# Pure_VCO.net
KiCad netlist of a schematic drawn in EAGLE
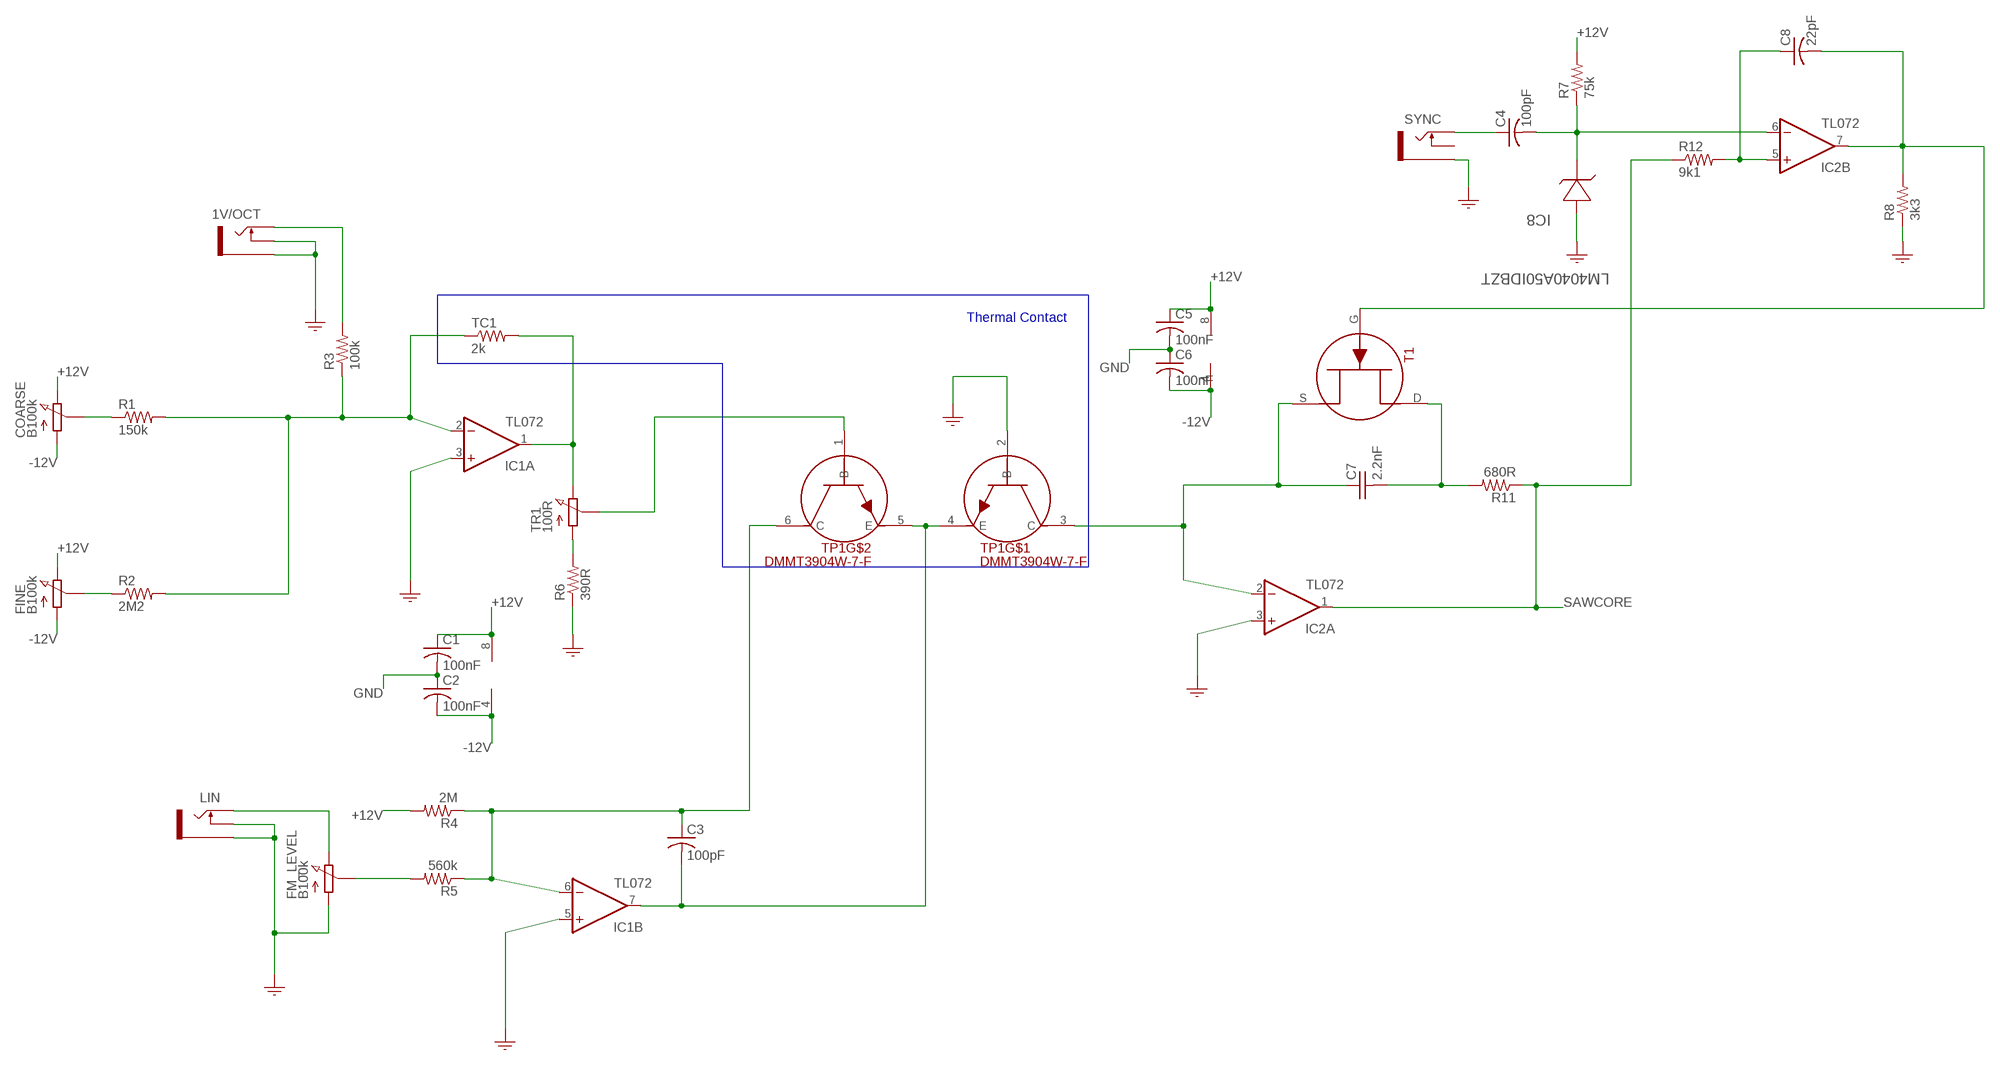
[diagram p0: schematic, sheet 1]
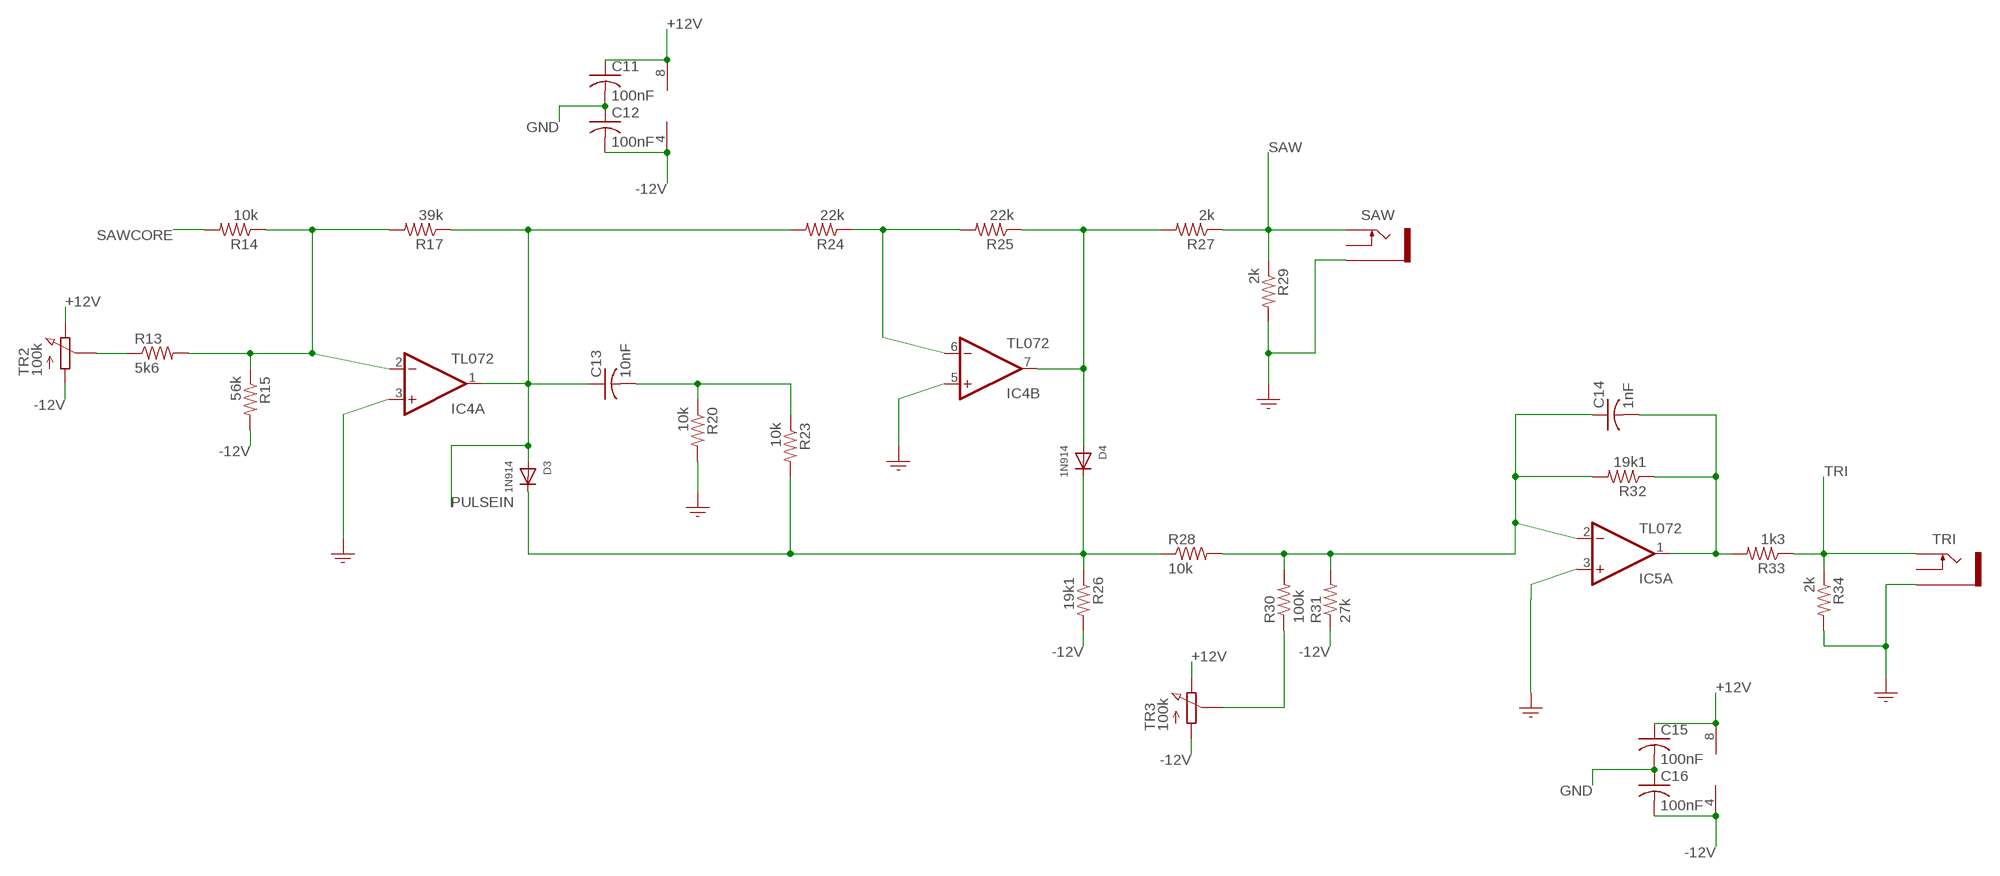
[diagram p1: schematic, sheet 2]
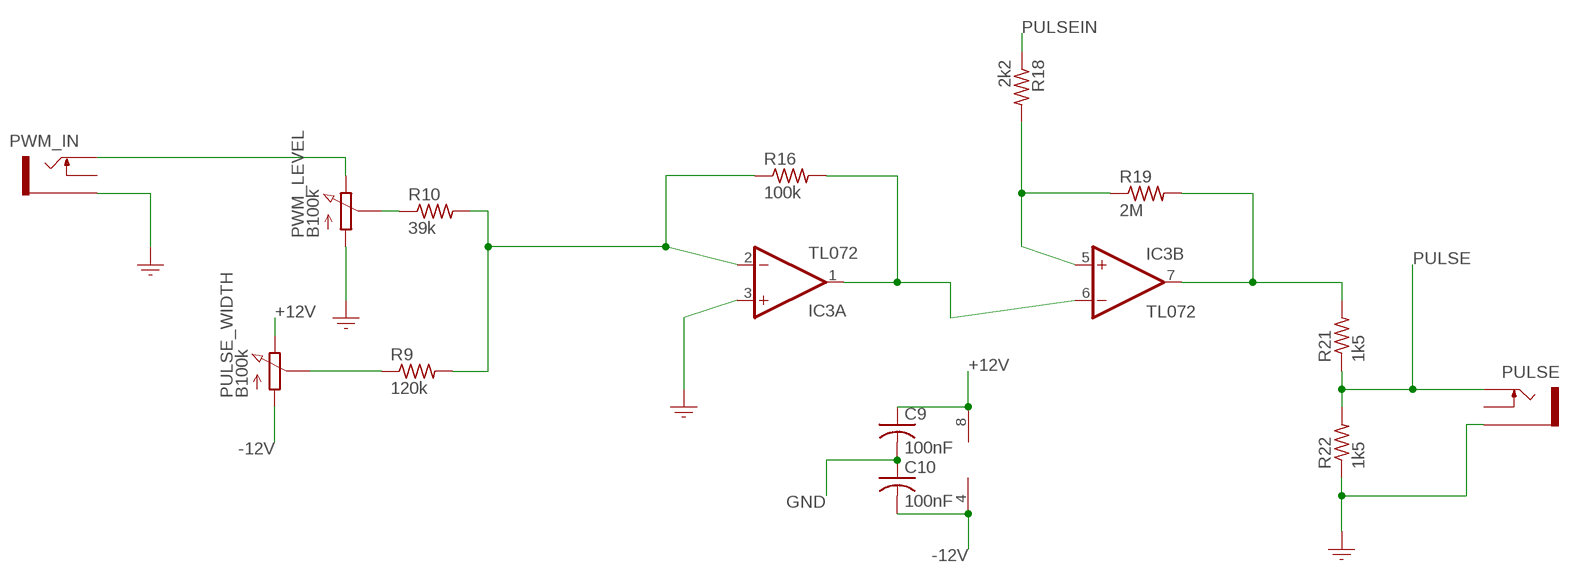
[diagram p2: schematic, sheet 3]
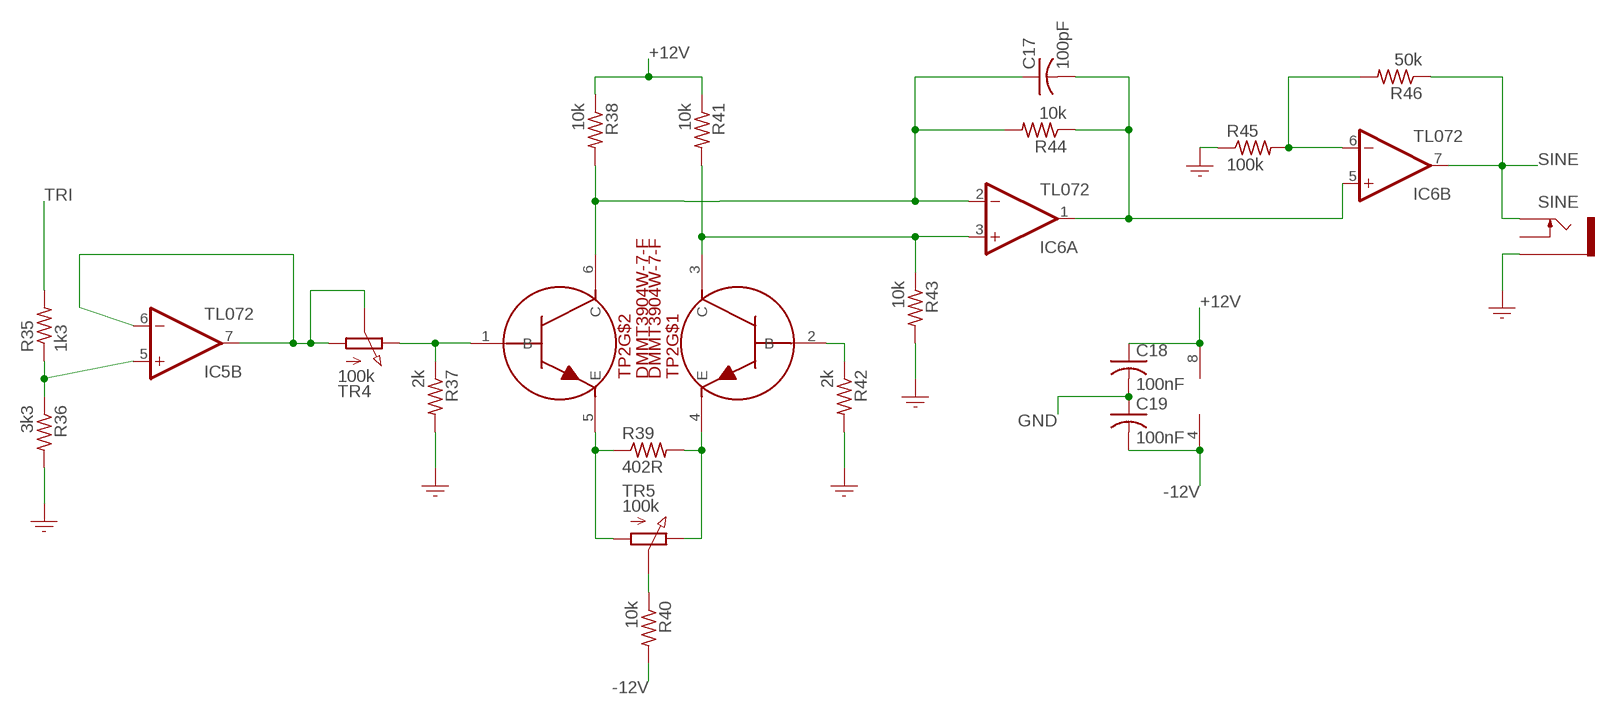
[diagram p3: schematic, sheet 4]
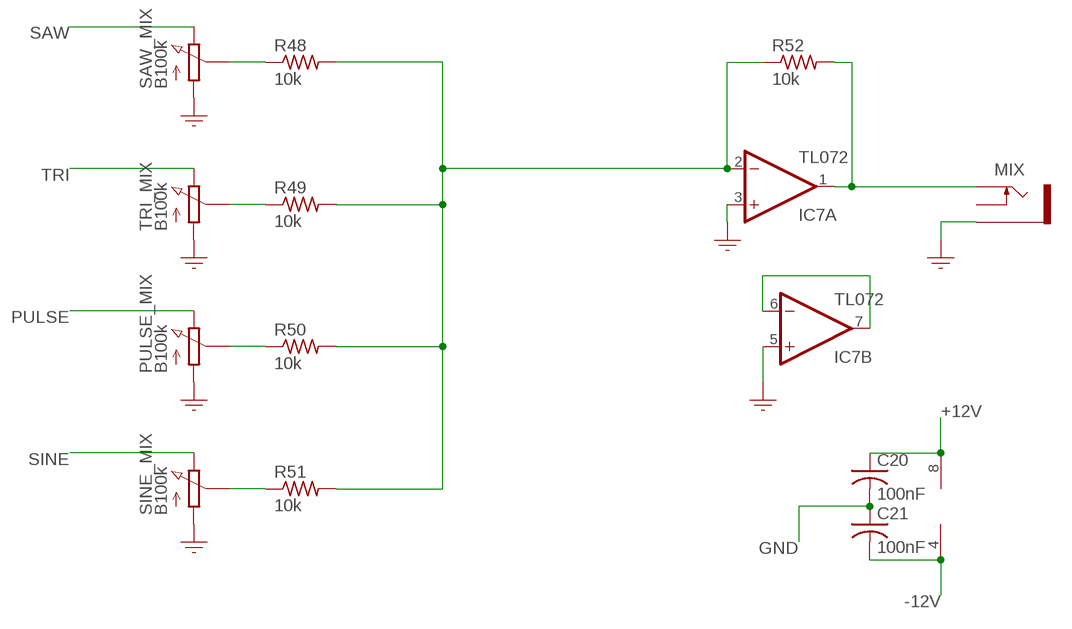
[diagram p4: schematic, sheet 5]
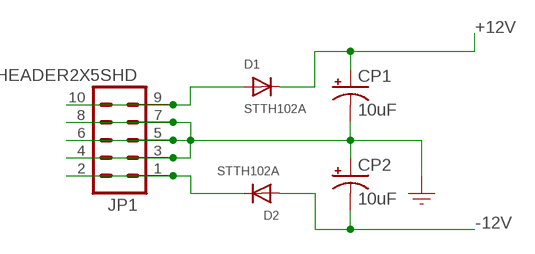
[diagram p5: schematic, sheet 6]

(export (version "E")
  (design (tool "Eeschema 10.0.6"))
  (components
    (comp (ref "1V/OCT")
      (value "PJ301M-12")
      (footprint "eagle-import:PJ301M-12")
      (libsource (lib "eagle-import") (part "SOCKET_MONO_3.5MMPJ301M-12"))
    )
    (comp (ref "C1")
      (value "100nF")
      (footprint "eagle-import:C0805")
      (libsource (lib "eagle-import") (part "CAPACITOR-USC0805"))
    )
    (comp (ref "C2")
      (value "100nF")
      (footprint "eagle-import:C0805")
      (libsource (lib "eagle-import") (part "CAPACITOR-USC0805"))
    )
    (comp (ref "C3")
      (value "100pF")
      (footprint "eagle-import:C0805")
      (libsource (lib "eagle-import") (part "CAPACITOR-USC0805"))
    )
    (comp (ref "C4")
      (value "100pF")
      (footprint "eagle-import:C0805")
      (libsource (lib "eagle-import") (part "CAPACITOR-USC0805"))
    )
    (comp (ref "C5")
      (value "100nF")
      (footprint "eagle-import:C0805")
      (libsource (lib "eagle-import") (part "CAPACITOR-USC0805"))
    )
    (comp (ref "C6")
      (value "100nF")
      (footprint "eagle-import:C0805")
      (libsource (lib "eagle-import") (part "CAPACITOR-USC0805"))
    )
    (comp (ref "C7")
      (value "2.2nF")
      (footprint "eagle-import:POLY_CAP")
      (libsource (lib "eagle-import") (part "CAPACITOR_POLYFILM"))
    )
    (comp (ref "C8")
      (value "22pF")
      (footprint "eagle-import:C0805")
      (libsource (lib "eagle-import") (part "CAPACITOR-USC0805"))
    )
    (comp (ref "COARSE")
      (value "B100k")
      (footprint "eagle-import:POT_9MM_RED_KNOB")
      (libsource (lib "eagle-import") (part "RESISTOR_VARIABLEPOT_9MM_RED_KNOB"))
    )
    (comp (ref "FINE")
      (value "B100k")
      (footprint "eagle-import:POT_9MM_RED_MXR_KNOB")
      (libsource (lib "eagle-import") (part "RESISTOR_VARIABLEPOT_9MM_RED_MXR_KNOB"))
    )
    (comp (ref "FM_LEVEL")
      (value "B100k")
      (footprint "eagle-import:POT_9MM_GREEN_KNOB")
      (libsource (lib "eagle-import") (part "RESISTOR_VARIABLEPOT_9MM_GREEN_KNOB"))
    )
    (comp (ref "IC1")
      (value "TL072")
      (footprint "eagle-import:SO08")
      (libsource (lib "eagle-import") (part "OPAMP_DUALD"))
    )
    (comp (ref "IC2")
      (value "TL072")
      (footprint "eagle-import:SO08")
      (libsource (lib "eagle-import") (part "OPAMP_DUALD"))
    )
    (comp (ref "IC8")
      (value "LM4040A50IDBZT")
      (footprint "eagle-import:SOT95P237X112-3N")
      (libsource (lib "eagle-import") (part "VOLTAGE_REF"))
    )
    (comp (ref "LIN")
      (value "PJ301M-12")
      (footprint "eagle-import:PJ301M-12")
      (libsource (lib "eagle-import") (part "SOCKET_MONO_3.5MMPJ301M-12"))
    )
    (comp (ref "R1")
      (value "150k")
      (footprint "eagle-import:R0805")
      (libsource (lib "eagle-import") (part "RESISTOR_USR0805"))
    )
    (comp (ref "R2")
      (value "2M2")
      (footprint "eagle-import:R0805")
      (libsource (lib "eagle-import") (part "RESISTOR_USR0805"))
    )
    (comp (ref "R3")
      (value "100k")
      (footprint "eagle-import:R0805")
      (libsource (lib "eagle-import") (part "RESISTOR_USR0805"))
    )
    (comp (ref "R4")
      (value "2M")
      (footprint "eagle-import:R0805")
      (libsource (lib "eagle-import") (part "RESISTOR_USR0805"))
    )
    (comp (ref "R5")
      (value "560k")
      (footprint "eagle-import:R0805")
      (libsource (lib "eagle-import") (part "RESISTOR_USR0805"))
    )
    (comp (ref "R6")
      (value "390R")
      (footprint "eagle-import:R0805")
      (libsource (lib "eagle-import") (part "RESISTOR_USR0805"))
    )
    (comp (ref "R7")
      (value "75k")
      (footprint "eagle-import:R0805")
      (libsource (lib "eagle-import") (part "RESISTOR_USR0805"))
    )
    (comp (ref "R8")
      (value "3k3")
      (footprint "eagle-import:R0805")
      (libsource (lib "eagle-import") (part "RESISTOR_USR0805"))
    )
    (comp (ref "R11")
      (value "680R")
      (footprint "eagle-import:R0805")
      (libsource (lib "eagle-import") (part "RESISTOR_USR0805"))
    )
    (comp (ref "R12")
      (value "9k1")
      (footprint "eagle-import:R0805")
      (libsource (lib "eagle-import") (part "RESISTOR_USR0805"))
    )
    (comp (ref "SYNC")
      (value "PJ301M-12")
      (footprint "eagle-import:PJ301M-12")
      (libsource (lib "eagle-import") (part "SOCKET_MONO_3.5MMPJ301M-12"))
    )
    (comp (ref "T1")
      (value "MMBFJ309")
      (footprint "eagle-import:N_CHN")
      (libsource (lib "eagle-import") (part "TRANSISTOR_JFET_N_CHN"))
    )
    (comp (ref "TC1")
      (value "2k")
      (footprint "eagle-import:0207_8.5")
      (libsource (lib "eagle-import") (part "RESISTOR_US0207/8.5"))
    )
    (comp (ref "TP1")
      (value "DMMT3904W-7-F")
      (footprint "eagle-import:TRANS_PAIR")
      (libsource (lib "eagle-import") (part "TRANSISTOR_PAIR_NPN"))
    )
    (comp (ref "TR1")
      (value "100R")
      (footprint "eagle-import:TRIMMER_TH")
      (libsource (lib "eagle-import") (part "RESISTOR_VARIABLETRIMMER_TH"))
    )
    (comp (ref "C11")
      (value "100nF")
      (footprint "eagle-import:C0805")
      (libsource (lib "eagle-import") (part "CAPACITOR-USC0805"))
    )
    (comp (ref "C12")
      (value "100nF")
      (footprint "eagle-import:C0805")
      (libsource (lib "eagle-import") (part "CAPACITOR-USC0805"))
    )
    (comp (ref "C13")
      (value "10nF")
      (footprint "eagle-import:C0805")
      (libsource (lib "eagle-import") (part "CAPACITOR-USC0805"))
    )
    (comp (ref "C14")
      (value "1nF")
      (footprint "eagle-import:C0805")
      (libsource (lib "eagle-import") (part "CAPACITOR-USC0805"))
    )
    (comp (ref "C15")
      (value "100nF")
      (footprint "eagle-import:C0805")
      (libsource (lib "eagle-import") (part "CAPACITOR-USC0805"))
    )
    (comp (ref "C16")
      (value "100nF")
      (footprint "eagle-import:C0805")
      (libsource (lib "eagle-import") (part "CAPACITOR-USC0805"))
    )
    (comp (ref "D3")
      (value "1N914")
      (footprint "eagle-import:SOD-323F")
      (libsource (lib "eagle-import") (part "DIODESOD-323F"))
    )
    (comp (ref "D4")
      (value "1N914")
      (footprint "eagle-import:SOD-323F")
      (libsource (lib "eagle-import") (part "DIODESOD-323F"))
    )
    (comp (ref "IC4")
      (value "TL072")
      (footprint "eagle-import:SO08")
      (libsource (lib "eagle-import") (part "OPAMP_DUALD"))
    )
    (comp (ref "IC5")
      (value "TL072")
      (footprint "eagle-import:SO08")
      (libsource (lib "eagle-import") (part "OPAMP_DUALD"))
    )
    (comp (ref "R13")
      (value "5k6")
      (footprint "eagle-import:R0805")
      (libsource (lib "eagle-import") (part "RESISTOR_USR0805"))
    )
    (comp (ref "R14")
      (value "10k")
      (footprint "eagle-import:R0805")
      (libsource (lib "eagle-import") (part "RESISTOR_USR0805"))
    )
    (comp (ref "R15")
      (value "56k")
      (footprint "eagle-import:R0805")
      (libsource (lib "eagle-import") (part "RESISTOR_USR0805"))
    )
    (comp (ref "R17")
      (value "39k")
      (footprint "eagle-import:R0805")
      (libsource (lib "eagle-import") (part "RESISTOR_USR0805"))
    )
    (comp (ref "R20")
      (value "10k")
      (footprint "eagle-import:R0805")
      (libsource (lib "eagle-import") (part "RESISTOR_USR0805"))
    )
    (comp (ref "R23")
      (value "10k")
      (footprint "eagle-import:R0805")
      (libsource (lib "eagle-import") (part "RESISTOR_USR0805"))
    )
    (comp (ref "R24")
      (value "22k")
      (footprint "eagle-import:R0805")
      (libsource (lib "eagle-import") (part "RESISTOR_USR0805"))
    )
    (comp (ref "R25")
      (value "22k")
      (footprint "eagle-import:R0805")
      (libsource (lib "eagle-import") (part "RESISTOR_USR0805"))
    )
    (comp (ref "R26")
      (value "19k1")
      (footprint "eagle-import:R0805")
      (libsource (lib "eagle-import") (part "RESISTOR_USR0805"))
    )
    (comp (ref "R27")
      (value "2k")
      (footprint "eagle-import:R0805")
      (libsource (lib "eagle-import") (part "RESISTOR_USR0805"))
    )
    (comp (ref "R28")
      (value "10k")
      (footprint "eagle-import:R0805")
      (libsource (lib "eagle-import") (part "RESISTOR_USR0805"))
    )
    (comp (ref "R29")
      (value "2k")
      (footprint "eagle-import:R0805")
      (libsource (lib "eagle-import") (part "RESISTOR_USR0805"))
    )
    (comp (ref "R30")
      (value "100k")
      (footprint "eagle-import:R0805")
      (libsource (lib "eagle-import") (part "RESISTOR_USR0805"))
    )
    (comp (ref "R31")
      (value "27k")
      (footprint "eagle-import:R0805")
      (libsource (lib "eagle-import") (part "RESISTOR_USR0805"))
    )
    (comp (ref "R32")
      (value "19k1")
      (footprint "eagle-import:R0805")
      (libsource (lib "eagle-import") (part "RESISTOR_USR0805"))
    )
    (comp (ref "R33")
      (value "1k3")
      (footprint "eagle-import:R0805")
      (libsource (lib "eagle-import") (part "RESISTOR_USR0805"))
    )
    (comp (ref "R34")
      (value "2k")
      (footprint "eagle-import:R0805")
      (libsource (lib "eagle-import") (part "RESISTOR_USR0805"))
    )
    (comp (ref "SAW")
      (value "PJ301M-12")
      (footprint "eagle-import:PJ301M-12")
      (libsource (lib "eagle-import") (part "SOCKET_MONO_3.5MMPJ301M-12"))
    )
    (comp (ref "TR2")
      (value "100k")
      (footprint "eagle-import:TRIMMER_TH")
      (libsource (lib "eagle-import") (part "RESISTOR_VARIABLETRIMMER_TH"))
    )
    (comp (ref "TR3")
      (value "100k")
      (footprint "eagle-import:TRIMMER_TH")
      (libsource (lib "eagle-import") (part "RESISTOR_VARIABLETRIMMER_TH"))
    )
    (comp (ref "TRI")
      (value "PJ301M-12")
      (footprint "eagle-import:PJ301M-12")
      (libsource (lib "eagle-import") (part "SOCKET_MONO_3.5MMPJ301M-12"))
    )
    (comp (ref "C17")
      (value "100pF")
      (footprint "eagle-import:C0805")
      (libsource (lib "eagle-import") (part "CAPACITOR-USC0805"))
    )
    (comp (ref "C18")
      (value "100nF")
      (footprint "eagle-import:C0805")
      (libsource (lib "eagle-import") (part "CAPACITOR-USC0805"))
    )
    (comp (ref "C19")
      (value "100nF")
      (footprint "eagle-import:C0805")
      (libsource (lib "eagle-import") (part "CAPACITOR-USC0805"))
    )
    (comp (ref "IC6")
      (value "TL072")
      (footprint "eagle-import:SO08")
      (libsource (lib "eagle-import") (part "OPAMP_DUALD"))
    )
    (comp (ref "R35")
      (value "1k3")
      (footprint "eagle-import:R0805")
      (libsource (lib "eagle-import") (part "RESISTOR_USR0805"))
    )
    (comp (ref "R36")
      (value "3k3")
      (footprint "eagle-import:R0805")
      (libsource (lib "eagle-import") (part "RESISTOR_USR0805"))
    )
    (comp (ref "R37")
      (value "2k")
      (footprint "eagle-import:R0805")
      (libsource (lib "eagle-import") (part "RESISTOR_USR0805"))
    )
    (comp (ref "R38")
      (value "10k")
      (footprint "eagle-import:R0805")
      (libsource (lib "eagle-import") (part "RESISTOR_USR0805"))
    )
    (comp (ref "R39")
      (value "402R")
      (footprint "eagle-import:R0805")
      (libsource (lib "eagle-import") (part "RESISTOR_USR0805"))
    )
    (comp (ref "R40")
      (value "10k")
      (footprint "eagle-import:R0805")
      (libsource (lib "eagle-import") (part "RESISTOR_USR0805"))
    )
    (comp (ref "R41")
      (value "10k")
      (footprint "eagle-import:R0805")
      (libsource (lib "eagle-import") (part "RESISTOR_USR0805"))
    )
    (comp (ref "R42")
      (value "2k")
      (footprint "eagle-import:R0805")
      (libsource (lib "eagle-import") (part "RESISTOR_USR0805"))
    )
    (comp (ref "R43")
      (value "10k")
      (footprint "eagle-import:R0805")
      (libsource (lib "eagle-import") (part "RESISTOR_USR0805"))
    )
    (comp (ref "R44")
      (value "10k")
      (footprint "eagle-import:R0805")
      (libsource (lib "eagle-import") (part "RESISTOR_USR0805"))
    )
    (comp (ref "R45")
      (value "100k")
      (footprint "eagle-import:R0805")
      (libsource (lib "eagle-import") (part "RESISTOR_USR0805"))
    )
    (comp (ref "R46")
      (value "50k")
      (footprint "eagle-import:R0805")
      (libsource (lib "eagle-import") (part "RESISTOR_USR0805"))
    )
    (comp (ref "SINE")
      (value "PJ301M-12")
      (footprint "eagle-import:PJ301M-12")
      (libsource (lib "eagle-import") (part "SOCKET_MONO_3.5MMPJ301M-12"))
    )
    (comp (ref "TP2")
      (value "DMMT3904W-7-F")
      (footprint "eagle-import:TRANS_PAIR")
      (libsource (lib "eagle-import") (part "TRANSISTOR_PAIR_NPN"))
    )
    (comp (ref "TR4")
      (value "100k")
      (footprint "eagle-import:TRIMMER_TH")
      (libsource (lib "eagle-import") (part "RESISTOR_VARIABLETRIMMER_TH"))
    )
    (comp (ref "TR5")
      (value "100k")
      (footprint "eagle-import:TRIMMER_TH")
      (libsource (lib "eagle-import") (part "RESISTOR_VARIABLETRIMMER_TH"))
    )
    (comp (ref "C20")
      (value "100nF")
      (footprint "eagle-import:C0805")
      (libsource (lib "eagle-import") (part "CAPACITOR-USC0805"))
    )
    (comp (ref "C21")
      (value "100nF")
      (footprint "eagle-import:C0805")
      (libsource (lib "eagle-import") (part "CAPACITOR-USC0805"))
    )
    (comp (ref "IC7")
      (value "TL072")
      (footprint "eagle-import:SO08")
      (libsource (lib "eagle-import") (part "OPAMP_DUALD"))
    )
    (comp (ref "MIX")
      (value "PJ301M-12")
      (footprint "eagle-import:PJ301M-12")
      (libsource (lib "eagle-import") (part "SOCKET_MONO_3.5MMPJ301M-12"))
    )
    (comp (ref "PULSE_MIX")
      (value "B100k")
      (footprint "eagle-import:POT_9MM_BLUE_KNOB")
      (libsource (lib "eagle-import") (part "RESISTOR_VARIABLEPOT_9MM_BLUE_KNOB"))
    )
    (comp (ref "R48")
      (value "10k")
      (footprint "eagle-import:R0805")
      (libsource (lib "eagle-import") (part "RESISTOR_USR0805"))
    )
    (comp (ref "R49")
      (value "10k")
      (footprint "eagle-import:R0805")
      (libsource (lib "eagle-import") (part "RESISTOR_USR0805"))
    )
    (comp (ref "R50")
      (value "10k")
      (footprint "eagle-import:R0805")
      (libsource (lib "eagle-import") (part "RESISTOR_USR0805"))
    )
    (comp (ref "R51")
      (value "10k")
      (footprint "eagle-import:R0805")
      (libsource (lib "eagle-import") (part "RESISTOR_USR0805"))
    )
    (comp (ref "R52")
      (value "10k")
      (footprint "eagle-import:R0805")
      (libsource (lib "eagle-import") (part "RESISTOR_USR0805"))
    )
    (comp (ref "SAW_MIX")
      (value "B100k")
      (footprint "eagle-import:POT_9MM_BLUE_KNOB")
      (libsource (lib "eagle-import") (part "RESISTOR_VARIABLEPOT_9MM_BLUE_KNOB"))
    )
    (comp (ref "SINE_MIX")
      (value "B100k")
      (footprint "eagle-import:POT_9MM_BLUE_KNOB")
      (libsource (lib "eagle-import") (part "RESISTOR_VARIABLEPOT_9MM_BLUE_KNOB"))
    )
    (comp (ref "TRI_MIX")
      (value "B100k")
      (footprint "eagle-import:POT_9MM_BLUE_KNOB")
      (libsource (lib "eagle-import") (part "RESISTOR_VARIABLEPOT_9MM_BLUE_KNOB"))
    )
    (comp (ref "C9")
      (value "100nF")
      (footprint "eagle-import:C0805")
      (libsource (lib "eagle-import") (part "CAPACITOR-USC0805"))
    )
    (comp (ref "C10")
      (value "100nF")
      (footprint "eagle-import:C0805")
      (libsource (lib "eagle-import") (part "CAPACITOR-USC0805"))
    )
    (comp (ref "IC3")
      (value "TL072")
      (footprint "eagle-import:SO08")
      (libsource (lib "eagle-import") (part "OPAMP_DUALD"))
    )
    (comp (ref "PULSE")
      (value "PJ301M-12")
      (footprint "eagle-import:PJ301M-12")
      (libsource (lib "eagle-import") (part "SOCKET_MONO_3.5MMPJ301M-12"))
    )
    (comp (ref "PULSE_WIDTH")
      (value "B100k")
      (footprint "eagle-import:POT_9MM_YELLOW_KNOB")
      (libsource (lib "eagle-import") (part "RESISTOR_VARIABLEPOT_9MM_YELLOW_KNOB"))
    )
    (comp (ref "PWM_IN")
      (value "PJ301M-12")
      (footprint "eagle-import:PJ301M-12")
      (libsource (lib "eagle-import") (part "SOCKET_MONO_3.5MMPJ301M-12"))
    )
    (comp (ref "PWM_LEVEL")
      (value "B100k")
      (footprint "eagle-import:POT_9MM_GREEN_KNOB")
      (libsource (lib "eagle-import") (part "RESISTOR_VARIABLEPOT_9MM_GREEN_KNOB"))
    )
    (comp (ref "R9")
      (value "120k")
      (footprint "eagle-import:R0805")
      (libsource (lib "eagle-import") (part "RESISTOR_USR0805"))
    )
    (comp (ref "R10")
      (value "39k")
      (footprint "eagle-import:R0805")
      (libsource (lib "eagle-import") (part "RESISTOR_USR0805"))
    )
    (comp (ref "R16")
      (value "100k")
      (footprint "eagle-import:R0805")
      (libsource (lib "eagle-import") (part "RESISTOR_USR0805"))
    )
    (comp (ref "R18")
      (value "2k2")
      (footprint "eagle-import:R0805")
      (libsource (lib "eagle-import") (part "RESISTOR_USR0805"))
    )
    (comp (ref "R19")
      (value "2M")
      (footprint "eagle-import:R0805")
      (libsource (lib "eagle-import") (part "RESISTOR_USR0805"))
    )
    (comp (ref "R21")
      (value "1k5")
      (footprint "eagle-import:R0805")
      (libsource (lib "eagle-import") (part "RESISTOR_USR0805"))
    )
    (comp (ref "R22")
      (value "1k5")
      (footprint "eagle-import:R0805")
      (libsource (lib "eagle-import") (part "RESISTOR_USR0805"))
    )
    (comp (ref "CP1")
      (value "10uF")
      (footprint "eagle-import:153CLV-0505")
      (libsource (lib "eagle-import") (part "CAPACITOR_POL-US153CLV-0505"))
    )
    (comp (ref "CP2")
      (value "10uF")
      (footprint "eagle-import:153CLV-0505")
      (libsource (lib "eagle-import") (part "CAPACITOR_POL-US153CLV-0505"))
    )
    (comp (ref "D1")
      (value "STTH102A")
      (footprint "eagle-import:SMADIODE")
      (libsource (lib "eagle-import") (part "DIODESMA"))
    )
    (comp (ref "D2")
      (value "STTH102A")
      (footprint "eagle-import:SMADIODE")
      (libsource (lib "eagle-import") (part "DIODESMA"))
    )
    (comp (ref "JP1")
      (value "HEADER2X5SHD")
      (footprint "eagle-import:2X5-SHROUDED")
      (libsource (lib "eagle-import") (part "HEADER2X5SHD"))
    )
  )
  (nets
    (net (code "1") (name "+12V") (class "Default")
      (node (ref "C1") (pin "1") (pinfunction "1_1") (pintype "passive"))
      (node (ref "C11") (pin "1") (pinfunction "1_1") (pintype "passive"))
      (node (ref "C15") (pin "1") (pinfunction "1_1") (pintype "passive"))
      (node (ref "C18") (pin "1") (pinfunction "1_1") (pintype "passive"))
      (node (ref "C20") (pin "1") (pinfunction "1_1") (pintype "passive"))
      (node (ref "C5") (pin "1") (pinfunction "1_1") (pintype "passive"))
      (node (ref "C9") (pin "1") (pinfunction "1_1") (pintype "passive"))
      (node (ref "COARSE") (pin "P$3") (pinfunction "3_P$3") (pintype "passive"))
      (node (ref "CP1") (pin "+") (pinfunction "+_+") (pintype "passive"))
      (node (ref "D1") (pin "C") (pinfunction "C_C") (pintype "passive"))
      (node (ref "FINE") (pin "P$3") (pinfunction "3_P$3") (pintype "passive"))
      (node (ref "IC1") (pin "8") (pinfunction "V+_8") (pintype "power_in"))
      (node (ref "IC2") (pin "8") (pinfunction "V+_8") (pintype "power_in"))
      (node (ref "IC3") (pin "8") (pinfunction "V+_8") (pintype "power_in"))
      (node (ref "IC4") (pin "8") (pinfunction "V+_8") (pintype "power_in"))
      (node (ref "IC5") (pin "8") (pinfunction "V+_8") (pintype "power_in"))
      (node (ref "IC6") (pin "8") (pinfunction "V+_8") (pintype "power_in"))
      (node (ref "IC7") (pin "8") (pinfunction "V+_8") (pintype "power_in"))
      (node (ref "PULSE_WIDTH") (pin "P$3") (pinfunction "3_P$3") (pintype "passive"))
      (node (ref "R38") (pin "1") (pinfunction "1_1") (pintype "passive"))
      (node (ref "R4") (pin "2") (pinfunction "2_2") (pintype "passive"))
      (node (ref "R41") (pin "1") (pinfunction "1_1") (pintype "passive"))
      (node (ref "R7") (pin "2") (pinfunction "2_2") (pintype "passive"))
      (node (ref "TR2") (pin "3") (pinfunction "3_3") (pintype "passive"))
      (node (ref "TR3") (pin "3") (pinfunction "3_3") (pintype "passive"))
    )
    (net (code "2") (name "-12V") (class "Default")
      (node (ref "C10") (pin "2") (pinfunction "2_2") (pintype "passive"))
      (node (ref "C12") (pin "2") (pinfunction "2_2") (pintype "passive"))
      (node (ref "C16") (pin "2") (pinfunction "2_2") (pintype "passive"))
      (node (ref "C19") (pin "2") (pinfunction "2_2") (pintype "passive"))
      (node (ref "C2") (pin "2") (pinfunction "2_2") (pintype "passive"))
      (node (ref "C21") (pin "2") (pinfunction "2_2") (pintype "passive"))
      (node (ref "C6") (pin "2") (pinfunction "2_2") (pintype "passive"))
      (node (ref "COARSE") (pin "P$1") (pinfunction "1_P$1") (pintype "passive"))
      (node (ref "CP2") (pin "-") (pinfunction "-_-") (pintype "passive"))
      (node (ref "D2") (pin "A") (pinfunction "A_A") (pintype "passive"))
      (node (ref "FINE") (pin "P$1") (pinfunction "1_P$1") (pintype "passive"))
      (node (ref "IC1") (pin "4") (pinfunction "V-_4") (pintype "power_in"))
      (node (ref "IC2") (pin "4") (pinfunction "V-_4") (pintype "power_in"))
      (node (ref "IC3") (pin "4") (pinfunction "V-_4") (pintype "power_in"))
      (node (ref "IC4") (pin "4") (pinfunction "V-_4") (pintype "power_in"))
      (node (ref "IC5") (pin "4") (pinfunction "V-_4") (pintype "power_in"))
      (node (ref "IC6") (pin "4") (pinfunction "V-_4") (pintype "power_in"))
      (node (ref "IC7") (pin "4") (pinfunction "V-_4") (pintype "power_in"))
      (node (ref "PULSE_WIDTH") (pin "P$1") (pinfunction "1_P$1") (pintype "passive"))
      (node (ref "R15") (pin "2") (pinfunction "2_2") (pintype "passive"))
      (node (ref "R26") (pin "2") (pinfunction "2_2") (pintype "passive"))
      (node (ref "R31") (pin "1") (pinfunction "1_1") (pintype "passive"))
      (node (ref "R40") (pin "2") (pinfunction "2_2") (pintype "passive"))
      (node (ref "TR2") (pin "1") (pinfunction "1_1") (pintype "passive"))
      (node (ref "TR3") (pin "1") (pinfunction "1_1") (pintype "passive"))
    )
    (net (code "3") (name "GND") (class "Default")
      (node (ref "1V/OCT") (pin "GND") (pinfunction "SLEEVE_GND") (pintype "passive"))
      (node (ref "1V/OCT") (pin "NORM") (pinfunction "SWITCH_NORM") (pintype "passive"))
      (node (ref "C1") (pin "2") (pinfunction "2_2") (pintype "passive"))
      (node (ref "C10") (pin "1") (pinfunction "1_1") (pintype "passive"))
      (node (ref "C11") (pin "2") (pinfunction "2_2") (pintype "passive"))
      (node (ref "C12") (pin "1") (pinfunction "1_1") (pintype "passive"))
      (node (ref "C15") (pin "2") (pinfunction "2_2") (pintype "passive"))
      (node (ref "C16") (pin "1") (pinfunction "1_1") (pintype "passive"))
      (node (ref "C18") (pin "2") (pinfunction "2_2") (pintype "passive"))
      (node (ref "C19") (pin "1") (pinfunction "1_1") (pintype "passive"))
      (node (ref "C2") (pin "1") (pinfunction "1_1") (pintype "passive"))
      (node (ref "C20") (pin "2") (pinfunction "2_2") (pintype "passive"))
      (node (ref "C21") (pin "1") (pinfunction "1_1") (pintype "passive"))
      (node (ref "C5") (pin "2") (pinfunction "2_2") (pintype "passive"))
      (node (ref "C6") (pin "1") (pinfunction "1_1") (pintype "passive"))
      (node (ref "C9") (pin "2") (pinfunction "2_2") (pintype "passive"))
      (node (ref "CP1") (pin "-") (pinfunction "-_-") (pintype "passive"))
      (node (ref "CP2") (pin "+") (pinfunction "+_+") (pintype "passive"))
      (node (ref "FM_LEVEL") (pin "P$1") (pinfunction "1_P$1") (pintype "passive"))
      (node (ref "IC1") (pin "3") (pinfunction "+IN_3") (pintype "input"))
      (node (ref "IC1") (pin "5") (pinfunction "+IN_5") (pintype "input"))
      (node (ref "IC2") (pin "3") (pinfunction "+IN_3") (pintype "input"))
      (node (ref "IC3") (pin "3") (pinfunction "+IN_3") (pintype "input"))
      (node (ref "IC4") (pin "3") (pinfunction "+IN_3") (pintype "input"))
      (node (ref "IC4") (pin "5") (pinfunction "+IN_5") (pintype "input"))
      (node (ref "IC5") (pin "3") (pinfunction "+IN_3") (pintype "input"))
      (node (ref "IC7") (pin "3") (pinfunction "+IN_3") (pintype "input"))
      (node (ref "IC7") (pin "5") (pinfunction "+IN_5") (pintype "input"))
      (node (ref "IC8") (pin "2") (pinfunction "ANODE_2") (pintype "input"))
      (node (ref "JP1") (pin "3") (pinfunction "3_3") (pintype "passive"))
      (node (ref "JP1") (pin "4") (pinfunction "4_4") (pintype "passive"))
      (node (ref "JP1") (pin "5") (pinfunction "5_5") (pintype "passive"))
      (node (ref "JP1") (pin "6") (pinfunction "6_6") (pintype "passive"))
      (node (ref "JP1") (pin "7") (pinfunction "7_7") (pintype "passive"))
      (node (ref "JP1") (pin "8") (pinfunction "8_8") (pintype "passive"))
      (node (ref "LIN") (pin "GND") (pinfunction "SLEEVE_GND") (pintype "passive"))
      (node (ref "LIN") (pin "NORM") (pinfunction "SWITCH_NORM") (pintype "passive"))
      (node (ref "MIX") (pin "GND") (pinfunction "SLEEVE_GND") (pintype "passive"))
      (node (ref "PULSE") (pin "GND") (pinfunction "SLEEVE_GND") (pintype "passive"))
      (node (ref "PULSE_MIX") (pin "P$1") (pinfunction "1_P$1") (pintype "passive"))
      (node (ref "PWM_IN") (pin "GND") (pinfunction "SLEEVE_GND") (pintype "passive"))
      (node (ref "PWM_LEVEL") (pin "P$1") (pinfunction "1_P$1") (pintype "passive"))
      (node (ref "R20") (pin "2") (pinfunction "2_2") (pintype "passive"))
      (node (ref "R22") (pin "1") (pinfunction "1_1") (pintype "passive"))
      (node (ref "R29") (pin "2") (pinfunction "2_2") (pintype "passive"))
      (node (ref "R34") (pin "2") (pinfunction "2_2") (pintype "passive"))
      (node (ref "R36") (pin "2") (pinfunction "2_2") (pintype "passive"))
      (node (ref "R37") (pin "2") (pinfunction "2_2") (pintype "passive"))
      (node (ref "R42") (pin "2") (pinfunction "2_2") (pintype "passive"))
      (node (ref "R43") (pin "2") (pinfunction "2_2") (pintype "passive"))
      (node (ref "R45") (pin "1") (pinfunction "1_1") (pintype "passive"))
      (node (ref "R6") (pin "1") (pinfunction "1_1") (pintype "passive"))
      (node (ref "R8") (pin "1") (pinfunction "1_1") (pintype "passive"))
      (node (ref "SAW") (pin "GND") (pinfunction "SLEEVE_GND") (pintype "passive"))
      (node (ref "SAW_MIX") (pin "P$1") (pinfunction "1_P$1") (pintype "passive"))
      (node (ref "SINE") (pin "GND") (pinfunction "SLEEVE_GND") (pintype "passive"))
      (node (ref "SINE_MIX") (pin "P$1") (pinfunction "1_P$1") (pintype "passive"))
      (node (ref "SYNC") (pin "GND") (pinfunction "SLEEVE_GND") (pintype "passive"))
      (node (ref "TP1") (pin "2") (pinfunction "B_2") (pintype "bidirectional"))
      (node (ref "TRI") (pin "GND") (pinfunction "SLEEVE_GND") (pintype "passive"))
      (node (ref "TRI_MIX") (pin "P$1") (pinfunction "1_P$1") (pintype "passive"))
    )
    (net (code "4") (name "Net-(1V/OCT-PadTIP)") (class "Default")
      (node (ref "1V/OCT") (pin "TIP") (pinfunction "TIP_TIP") (pintype "passive"))
      (node (ref "R3") (pin "2") (pinfunction "2_2") (pintype "passive"))
    )
    (net (code "5") (name "Net-(C4-Pad1)") (class "Default")
      (node (ref "C4") (pin "1") (pinfunction "1_1") (pintype "passive"))
      (node (ref "SYNC") (pin "TIP") (pinfunction "TIP_TIP") (pintype "passive"))
    )
    (net (code "6") (name "Net-(C7-+)") (class "Default")
      (node (ref "C7") (pin "1") (pinfunction "+_1") (pintype "passive"))
      (node (ref "IC2") (pin "2") (pinfunction "-IN_2") (pintype "input"))
      (node (ref "T1") (pin "S") (pinfunction "S_S") (pintype "bidirectional"))
      (node (ref "TP1") (pin "3") (pinfunction "C_3") (pintype "bidirectional"))
    )
    (net (code "7") (name "Net-(C7--)") (class "Default")
      (node (ref "C7") (pin "2") (pinfunction "-_2") (pintype "passive"))
      (node (ref "R11") (pin "2") (pinfunction "2_2") (pintype "passive"))
      (node (ref "T1") (pin "D") (pinfunction "D_D") (pintype "bidirectional"))
    )
    (net (code "8") (name "Net-(C13-Pad2)") (class "Default")
      (node (ref "C13") (pin "2") (pinfunction "2_2") (pintype "passive"))
      (node (ref "R20") (pin "1") (pinfunction "1_1") (pintype "passive"))
      (node (ref "R23") (pin "1") (pinfunction "1_1") (pintype "passive"))
    )
    (net (code "9") (name "Net-(COARSE-2)") (class "Default")
      (node (ref "COARSE") (pin "P$2") (pinfunction "2_P$2") (pintype "passive"))
      (node (ref "R1") (pin "1") (pinfunction "1_1") (pintype "passive"))
    )
    (net (code "10") (name "Net-(D1-PadA)") (class "Default")
      (node (ref "D1") (pin "A") (pinfunction "A_A") (pintype "passive"))
      (node (ref "JP1") (pin "10") (pinfunction "10_10") (pintype "passive"))
      (node (ref "JP1") (pin "9") (pinfunction "9_9") (pintype "passive"))
    )
    (net (code "11") (name "Net-(D2-PadC)") (class "Default")
      (node (ref "D2") (pin "C") (pinfunction "C_C") (pintype "passive"))
      (node (ref "JP1") (pin "1") (pinfunction "1_1") (pintype "passive"))
      (node (ref "JP1") (pin "2") (pinfunction "2_2") (pintype "passive"))
    )
    (net (code "12") (name "Net-(D3-PadC)") (class "Default")
      (node (ref "D3") (pin "C") (pinfunction "C_C") (pintype "passive"))
      (node (ref "D4") (pin "C") (pinfunction "C_C") (pintype "passive"))
      (node (ref "R23") (pin "2") (pinfunction "2_2") (pintype "passive"))
      (node (ref "R26") (pin "1") (pinfunction "1_1") (pintype "passive"))
      (node (ref "R28") (pin "1") (pinfunction "1_1") (pintype "passive"))
    )
    (net (code "13") (name "Net-(FINE-2)") (class "Default")
      (node (ref "FINE") (pin "P$2") (pinfunction "2_P$2") (pintype "passive"))
      (node (ref "R2") (pin "1") (pinfunction "1_1") (pintype "passive"))
    )
    (net (code "14") (name "Net-(FM_LEVEL-2)") (class "Default")
      (node (ref "FM_LEVEL") (pin "P$2") (pinfunction "2_P$2") (pintype "passive"))
      (node (ref "R5") (pin "2") (pinfunction "2_2") (pintype "passive"))
    )
    (net (code "15") (name "Net-(FM_LEVEL-3)") (class "Default")
      (node (ref "FM_LEVEL") (pin "P$3") (pinfunction "3_P$3") (pintype "passive"))
      (node (ref "LIN") (pin "TIP") (pinfunction "TIP_TIP") (pintype "passive"))
    )
    (net (code "16") (name "Net-(IC1A--IN)") (class "Default")
      (node (ref "IC1") (pin "2") (pinfunction "-IN_2") (pintype "input"))
      (node (ref "R1") (pin "2") (pinfunction "2_2") (pintype "passive"))
      (node (ref "R2") (pin "2") (pinfunction "2_2") (pintype "passive"))
      (node (ref "R3") (pin "1") (pinfunction "1_1") (pintype "passive"))
      (node (ref "TC1") (pin "1") (pinfunction "1_1") (pintype "passive"))
    )
    (net (code "17") (name "Net-(IC1A-OUT)") (class "Default")
      (node (ref "IC1") (pin "1") (pinfunction "OUT_1") (pintype "output"))
      (node (ref "TC1") (pin "2") (pinfunction "2_2") (pintype "passive"))
      (node (ref "TR1") (pin "3") (pinfunction "3_3") (pintype "passive"))
    )
    (net (code "18") (name "Net-(IC1B--IN)") (class "Default")
      (node (ref "C3") (pin "1") (pinfunction "1_1") (pintype "passive"))
      (node (ref "IC1") (pin "6") (pinfunction "-IN_6") (pintype "input"))
      (node (ref "R4") (pin "1") (pinfunction "1_1") (pintype "passive"))
      (node (ref "R5") (pin "1") (pinfunction "1_1") (pintype "passive"))
      (node (ref "TP1") (pin "6") (pinfunction "C_6") (pintype "bidirectional"))
    )
    (net (code "19") (name "Net-(IC1B-OUT)") (class "Default")
      (node (ref "C3") (pin "2") (pinfunction "2_2") (pintype "passive"))
      (node (ref "IC1") (pin "7") (pinfunction "OUT_7") (pintype "output"))
      (node (ref "TP1") (pin "4") (pinfunction "E_4") (pintype "bidirectional"))
      (node (ref "TP1") (pin "5") (pinfunction "E_5") (pintype "bidirectional"))
    )
    (net (code "20") (name "Net-(IC2B-+IN)") (class "Default")
      (node (ref "C8") (pin "1") (pinfunction "1_1") (pintype "passive"))
      (node (ref "IC2") (pin "5") (pinfunction "+IN_5") (pintype "input"))
      (node (ref "R12") (pin "2") (pinfunction "2_2") (pintype "passive"))
    )
    (net (code "21") (name "Net-(IC2B--IN)") (class "Default")
      (node (ref "C4") (pin "2") (pinfunction "2_2") (pintype "passive"))
      (node (ref "IC2") (pin "6") (pinfunction "-IN_6") (pintype "input"))
      (node (ref "IC8") (pin "1") (pinfunction "CATHODE_1") (pintype "output"))
      (node (ref "R7") (pin "1") (pinfunction "1_1") (pintype "passive"))
    )
    (net (code "22") (name "Net-(IC2B-OUT)") (class "Default")
      (node (ref "C8") (pin "2") (pinfunction "2_2") (pintype "passive"))
      (node (ref "IC2") (pin "7") (pinfunction "OUT_7") (pintype "output"))
      (node (ref "R8") (pin "2") (pinfunction "2_2") (pintype "passive"))
      (node (ref "T1") (pin "G") (pinfunction "G_G") (pintype "bidirectional"))
    )
    (net (code "23") (name "Net-(IC3A--IN)") (class "Default")
      (node (ref "IC3") (pin "2") (pinfunction "-IN_2") (pintype "input"))
      (node (ref "R10") (pin "2") (pinfunction "2_2") (pintype "passive"))
      (node (ref "R16") (pin "1") (pinfunction "1_1") (pintype "passive"))
      (node (ref "R9") (pin "2") (pinfunction "2_2") (pintype "passive"))
    )
    (net (code "24") (name "Net-(IC3A-OUT)") (class "Default")
      (node (ref "IC3") (pin "1") (pinfunction "OUT_1") (pintype "output"))
      (node (ref "IC3") (pin "6") (pinfunction "-IN_6") (pintype "input"))
      (node (ref "R16") (pin "2") (pinfunction "2_2") (pintype "passive"))
    )
    (net (code "25") (name "Net-(IC3B-+IN)") (class "Default")
      (node (ref "IC3") (pin "5") (pinfunction "+IN_5") (pintype "input"))
      (node (ref "R18") (pin "2") (pinfunction "2_2") (pintype "passive"))
      (node (ref "R19") (pin "1") (pinfunction "1_1") (pintype "passive"))
    )
    (net (code "26") (name "Net-(IC3B-OUT)") (class "Default")
      (node (ref "IC3") (pin "7") (pinfunction "OUT_7") (pintype "output"))
      (node (ref "R19") (pin "2") (pinfunction "2_2") (pintype "passive"))
      (node (ref "R21") (pin "2") (pinfunction "2_2") (pintype "passive"))
    )
    (net (code "27") (name "Net-(IC4A--IN)") (class "Default")
      (node (ref "IC4") (pin "2") (pinfunction "-IN_2") (pintype "input"))
      (node (ref "R13") (pin "2") (pinfunction "2_2") (pintype "passive"))
      (node (ref "R14") (pin "1") (pinfunction "1_1") (pintype "passive"))
      (node (ref "R15") (pin "1") (pinfunction "1_1") (pintype "passive"))
      (node (ref "R17") (pin "2") (pinfunction "2_2") (pintype "passive"))
    )
    (net (code "28") (name "Net-(IC4B--IN)") (class "Default")
      (node (ref "IC4") (pin "6") (pinfunction "-IN_6") (pintype "input"))
      (node (ref "R24") (pin "1") (pinfunction "1_1") (pintype "passive"))
      (node (ref "R25") (pin "2") (pinfunction "2_2") (pintype "passive"))
    )
    (net (code "29") (name "Net-(IC4B-OUT)") (class "Default")
      (node (ref "D4") (pin "A") (pinfunction "A_A") (pintype "passive"))
      (node (ref "IC4") (pin "7") (pinfunction "OUT_7") (pintype "output"))
      (node (ref "R25") (pin "1") (pinfunction "1_1") (pintype "passive"))
      (node (ref "R27") (pin "2") (pinfunction "2_2") (pintype "passive"))
    )
    (net (code "30") (name "Net-(IC5A--IN)") (class "Default")
      (node (ref "C14") (pin "1") (pinfunction "1_1") (pintype "passive"))
      (node (ref "IC5") (pin "2") (pinfunction "-IN_2") (pintype "input"))
      (node (ref "R28") (pin "2") (pinfunction "2_2") (pintype "passive"))
      (node (ref "R30") (pin "2") (pinfunction "2_2") (pintype "passive"))
      (node (ref "R31") (pin "2") (pinfunction "2_2") (pintype "passive"))
      (node (ref "R32") (pin "2") (pinfunction "2_2") (pintype "passive"))
    )
    (net (code "31") (name "Net-(IC5A-OUT)") (class "Default")
      (node (ref "C14") (pin "2") (pinfunction "2_2") (pintype "passive"))
      (node (ref "IC5") (pin "1") (pinfunction "OUT_1") (pintype "output"))
      (node (ref "R32") (pin "1") (pinfunction "1_1") (pintype "passive"))
      (node (ref "R33") (pin "2") (pinfunction "2_2") (pintype "passive"))
    )
    (net (code "32") (name "Net-(IC5B-+IN)") (class "Default")
      (node (ref "IC5") (pin "5") (pinfunction "+IN_5") (pintype "input"))
      (node (ref "R35") (pin "1") (pinfunction "1_1") (pintype "passive"))
      (node (ref "R36") (pin "1") (pinfunction "1_1") (pintype "passive"))
    )
    (net (code "33") (name "Net-(IC5B--IN)") (class "Default")
      (node (ref "IC5") (pin "6") (pinfunction "-IN_6") (pintype "input"))
      (node (ref "IC5") (pin "7") (pinfunction "OUT_7") (pintype "output"))
      (node (ref "TR4") (pin "1") (pinfunction "1_1") (pintype "passive"))
      (node (ref "TR4") (pin "2") (pinfunction "2_2") (pintype "passive"))
    )
    (net (code "34") (name "Net-(IC6A-+IN)") (class "Default")
      (node (ref "IC6") (pin "3") (pinfunction "+IN_3") (pintype "input"))
      (node (ref "R41") (pin "2") (pinfunction "2_2") (pintype "passive"))
      (node (ref "R43") (pin "1") (pinfunction "1_1") (pintype "passive"))
      (node (ref "TP2") (pin "3") (pinfunction "C_3") (pintype "bidirectional"))
    )
    (net (code "35") (name "Net-(IC6A--IN)") (class "Default")
      (node (ref "C17") (pin "1") (pinfunction "1_1") (pintype "passive"))
      (node (ref "IC6") (pin "2") (pinfunction "-IN_2") (pintype "input"))
      (node (ref "R38") (pin "2") (pinfunction "2_2") (pintype "passive"))
      (node (ref "R44") (pin "2") (pinfunction "2_2") (pintype "passive"))
      (node (ref "TP2") (pin "6") (pinfunction "C_6") (pintype "bidirectional"))
    )
    (net (code "36") (name "Net-(IC6A-OUT)") (class "Default")
      (node (ref "C17") (pin "2") (pinfunction "2_2") (pintype "passive"))
      (node (ref "IC6") (pin "1") (pinfunction "OUT_1") (pintype "output"))
      (node (ref "IC6") (pin "5") (pinfunction "+IN_5") (pintype "input"))
      (node (ref "R44") (pin "1") (pinfunction "1_1") (pintype "passive"))
    )
    (net (code "37") (name "Net-(IC6B--IN)") (class "Default")
      (node (ref "IC6") (pin "6") (pinfunction "-IN_6") (pintype "input"))
      (node (ref "R45") (pin "2") (pinfunction "2_2") (pintype "passive"))
      (node (ref "R46") (pin "2") (pinfunction "2_2") (pintype "passive"))
    )
    (net (code "38") (name "Net-(IC7A--IN)") (class "Default")
      (node (ref "IC7") (pin "2") (pinfunction "-IN_2") (pintype "input"))
      (node (ref "R48") (pin "2") (pinfunction "2_2") (pintype "passive"))
      (node (ref "R49") (pin "2") (pinfunction "2_2") (pintype "passive"))
      (node (ref "R50") (pin "2") (pinfunction "2_2") (pintype "passive"))
      (node (ref "R51") (pin "2") (pinfunction "2_2") (pintype "passive"))
      (node (ref "R52") (pin "1") (pinfunction "1_1") (pintype "passive"))
    )
    (net (code "39") (name "Net-(IC7A-OUT)") (class "Default")
      (node (ref "IC7") (pin "1") (pinfunction "OUT_1") (pintype "output"))
      (node (ref "MIX") (pin "TIP") (pinfunction "TIP_TIP") (pintype "passive"))
      (node (ref "R52") (pin "2") (pinfunction "2_2") (pintype "passive"))
    )
    (net (code "40") (name "Net-(IC7B--IN)") (class "Default")
      (node (ref "IC7") (pin "6") (pinfunction "-IN_6") (pintype "input"))
      (node (ref "IC7") (pin "7") (pinfunction "OUT_7") (pintype "output"))
    )
    (net (code "41") (name "Net-(PULSE_MIX-2)") (class "Default")
      (node (ref "PULSE_MIX") (pin "P$2") (pinfunction "2_P$2") (pintype "passive"))
      (node (ref "R50") (pin "1") (pinfunction "1_1") (pintype "passive"))
    )
    (net (code "42") (name "Net-(PULSE_WIDTH-2)") (class "Default")
      (node (ref "PULSE_WIDTH") (pin "P$2") (pinfunction "2_P$2") (pintype "passive"))
      (node (ref "R9") (pin "1") (pinfunction "1_1") (pintype "passive"))
    )
    (net (code "43") (name "Net-(PWM_LEVEL-2)") (class "Default")
      (node (ref "PWM_LEVEL") (pin "P$2") (pinfunction "2_P$2") (pintype "passive"))
      (node (ref "R10") (pin "1") (pinfunction "1_1") (pintype "passive"))
    )
    (net (code "44") (name "Net-(PWM_LEVEL-3)") (class "Default")
      (node (ref "PWM_IN") (pin "TIP") (pinfunction "TIP_TIP") (pintype "passive"))
      (node (ref "PWM_LEVEL") (pin "P$3") (pinfunction "3_P$3") (pintype "passive"))
    )
    (net (code "45") (name "Net-(R6-Pad2)") (class "Default")
      (node (ref "R6") (pin "2") (pinfunction "2_2") (pintype "passive"))
      (node (ref "TR1") (pin "1") (pinfunction "1_1") (pintype "passive"))
    )
    (net (code "46") (name "Net-(R13-Pad1)") (class "Default")
      (node (ref "R13") (pin "1") (pinfunction "1_1") (pintype "passive"))
      (node (ref "TR2") (pin "2") (pinfunction "2_2") (pintype "passive"))
    )
    (net (code "47") (name "Net-(R30-Pad1)") (class "Default")
      (node (ref "R30") (pin "1") (pinfunction "1_1") (pintype "passive"))
      (node (ref "TR3") (pin "2") (pinfunction "2_2") (pintype "passive"))
    )
    (net (code "48") (name "Net-(R40-Pad1)") (class "Default")
      (node (ref "R40") (pin "1") (pinfunction "1_1") (pintype "passive"))
      (node (ref "TR5") (pin "2") (pinfunction "2_2") (pintype "passive"))
    )
    (net (code "49") (name "Net-(SAW_MIX-2)") (class "Default")
      (node (ref "R48") (pin "1") (pinfunction "1_1") (pintype "passive"))
      (node (ref "SAW_MIX") (pin "P$2") (pinfunction "2_P$2") (pintype "passive"))
    )
    (net (code "50") (name "Net-(SINE_MIX-2)") (class "Default")
      (node (ref "R51") (pin "1") (pinfunction "1_1") (pintype "passive"))
      (node (ref "SINE_MIX") (pin "P$2") (pinfunction "2_P$2") (pintype "passive"))
    )
    (net (code "51") (name "Net-(TP1B-B)") (class "Default")
      (node (ref "TP1") (pin "1") (pinfunction "B_1") (pintype "bidirectional"))
      (node (ref "TR1") (pin "2") (pinfunction "2_2") (pintype "passive"))
    )
    (net (code "52") (name "Net-(TP2A-B)") (class "Default")
      (node (ref "R42") (pin "1") (pinfunction "1_1") (pintype "passive"))
      (node (ref "TP2") (pin "2") (pinfunction "B_2") (pintype "bidirectional"))
    )
    (net (code "53") (name "Net-(TP2A-E)") (class "Default")
      (node (ref "R39") (pin "2") (pinfunction "2_2") (pintype "passive"))
      (node (ref "TP2") (pin "4") (pinfunction "E_4") (pintype "bidirectional"))
      (node (ref "TR5") (pin "3") (pinfunction "3_3") (pintype "passive"))
    )
    (net (code "54") (name "Net-(TP2B-B)") (class "Default")
      (node (ref "R37") (pin "1") (pinfunction "1_1") (pintype "passive"))
      (node (ref "TP2") (pin "1") (pinfunction "B_1") (pintype "bidirectional"))
      (node (ref "TR4") (pin "3") (pinfunction "3_3") (pintype "passive"))
    )
    (net (code "55") (name "Net-(TP2B-E)") (class "Default")
      (node (ref "R39") (pin "1") (pinfunction "1_1") (pintype "passive"))
      (node (ref "TP2") (pin "5") (pinfunction "E_5") (pintype "bidirectional"))
      (node (ref "TR5") (pin "1") (pinfunction "1_1") (pintype "passive"))
    )
    (net (code "56") (name "Net-(TRI_MIX-2)") (class "Default")
      (node (ref "R49") (pin "1") (pinfunction "1_1") (pintype "passive"))
      (node (ref "TRI_MIX") (pin "P$2") (pinfunction "2_P$2") (pintype "passive"))
    )
    (net (code "57") (name "PULSE") (class "Default")
      (node (ref "PULSE") (pin "TIP") (pinfunction "TIP_TIP") (pintype "passive"))
      (node (ref "PULSE_MIX") (pin "P$3") (pinfunction "3_P$3") (pintype "passive"))
      (node (ref "R21") (pin "1") (pinfunction "1_1") (pintype "passive"))
      (node (ref "R22") (pin "2") (pinfunction "2_2") (pintype "passive"))
    )
    (net (code "58") (name "PULSEIN") (class "Default")
      (node (ref "C13") (pin "1") (pinfunction "1_1") (pintype "passive"))
      (node (ref "D3") (pin "A") (pinfunction "A_A") (pintype "passive"))
      (node (ref "IC4") (pin "1") (pinfunction "OUT_1") (pintype "output"))
      (node (ref "R17") (pin "1") (pinfunction "1_1") (pintype "passive"))
      (node (ref "R18") (pin "1") (pinfunction "1_1") (pintype "passive"))
      (node (ref "R24") (pin "2") (pinfunction "2_2") (pintype "passive"))
    )
    (net (code "59") (name "SAW") (class "Default")
      (node (ref "R27") (pin "1") (pinfunction "1_1") (pintype "passive"))
      (node (ref "R29") (pin "1") (pinfunction "1_1") (pintype "passive"))
      (node (ref "SAW") (pin "TIP") (pinfunction "TIP_TIP") (pintype "passive"))
      (node (ref "SAW_MIX") (pin "P$3") (pinfunction "3_P$3") (pintype "passive"))
    )
    (net (code "60") (name "SAWCORE") (class "Default")
      (node (ref "IC2") (pin "1") (pinfunction "OUT_1") (pintype "output"))
      (node (ref "R11") (pin "1") (pinfunction "1_1") (pintype "passive"))
      (node (ref "R12") (pin "1") (pinfunction "1_1") (pintype "passive"))
      (node (ref "R14") (pin "2") (pinfunction "2_2") (pintype "passive"))
    )
    (net (code "61") (name "SINE") (class "Default")
      (node (ref "IC6") (pin "7") (pinfunction "OUT_7") (pintype "output"))
      (node (ref "R46") (pin "1") (pinfunction "1_1") (pintype "passive"))
      (node (ref "SINE") (pin "TIP") (pinfunction "TIP_TIP") (pintype "passive"))
      (node (ref "SINE_MIX") (pin "P$3") (pinfunction "3_P$3") (pintype "passive"))
    )
    (net (code "62") (name "TRI") (class "Default")
      (node (ref "R33") (pin "1") (pinfunction "1_1") (pintype "passive"))
      (node (ref "R34") (pin "1") (pinfunction "1_1") (pintype "passive"))
      (node (ref "R35") (pin "2") (pinfunction "2_2") (pintype "passive"))
      (node (ref "TRI") (pin "TIP") (pinfunction "TIP_TIP") (pintype "passive"))
      (node (ref "TRI_MIX") (pin "P$3") (pinfunction "3_P$3") (pintype "passive"))
    )
    (net (code "63") (name "unconnected-(IC8-NC-Pad3)") (class "Default")
      (node (ref "IC8") (pin "3") (pinfunction "NC_3") (pintype "no_connect"))
    )
    (net (code "64") (name "unconnected-(MIX-SWITCH-PadNORM)") (class "Default")
      (node (ref "MIX") (pin "NORM") (pinfunction "SWITCH_NORM") (pintype "passive"))
    )
    (net (code "65") (name "unconnected-(PULSE-SWITCH-PadNORM)") (class "Default")
      (node (ref "PULSE") (pin "NORM") (pinfunction "SWITCH_NORM") (pintype "passive"))
    )
    (net (code "66") (name "unconnected-(PWM_IN-SWITCH-PadNORM)") (class "Default")
      (node (ref "PWM_IN") (pin "NORM") (pinfunction "SWITCH_NORM") (pintype "passive"))
    )
    (net (code "67") (name "unconnected-(SAW-SWITCH-PadNORM)") (class "Default")
      (node (ref "SAW") (pin "NORM") (pinfunction "SWITCH_NORM") (pintype "passive"))
    )
    (net (code "68") (name "unconnected-(SINE-SWITCH-PadNORM)") (class "Default")
      (node (ref "SINE") (pin "NORM") (pinfunction "SWITCH_NORM") (pintype "passive"))
    )
    (net (code "69") (name "unconnected-(SYNC-SWITCH-PadNORM)") (class "Default")
      (node (ref "SYNC") (pin "NORM") (pinfunction "SWITCH_NORM") (pintype "passive"))
    )
    (net (code "70") (name "unconnected-(TRI-SWITCH-PadNORM)") (class "Default")
      (node (ref "TRI") (pin "NORM") (pinfunction "SWITCH_NORM") (pintype "passive"))
    )
  )
)
